# main.net
KiCad netlist of a schematic drawn in Altium Designer
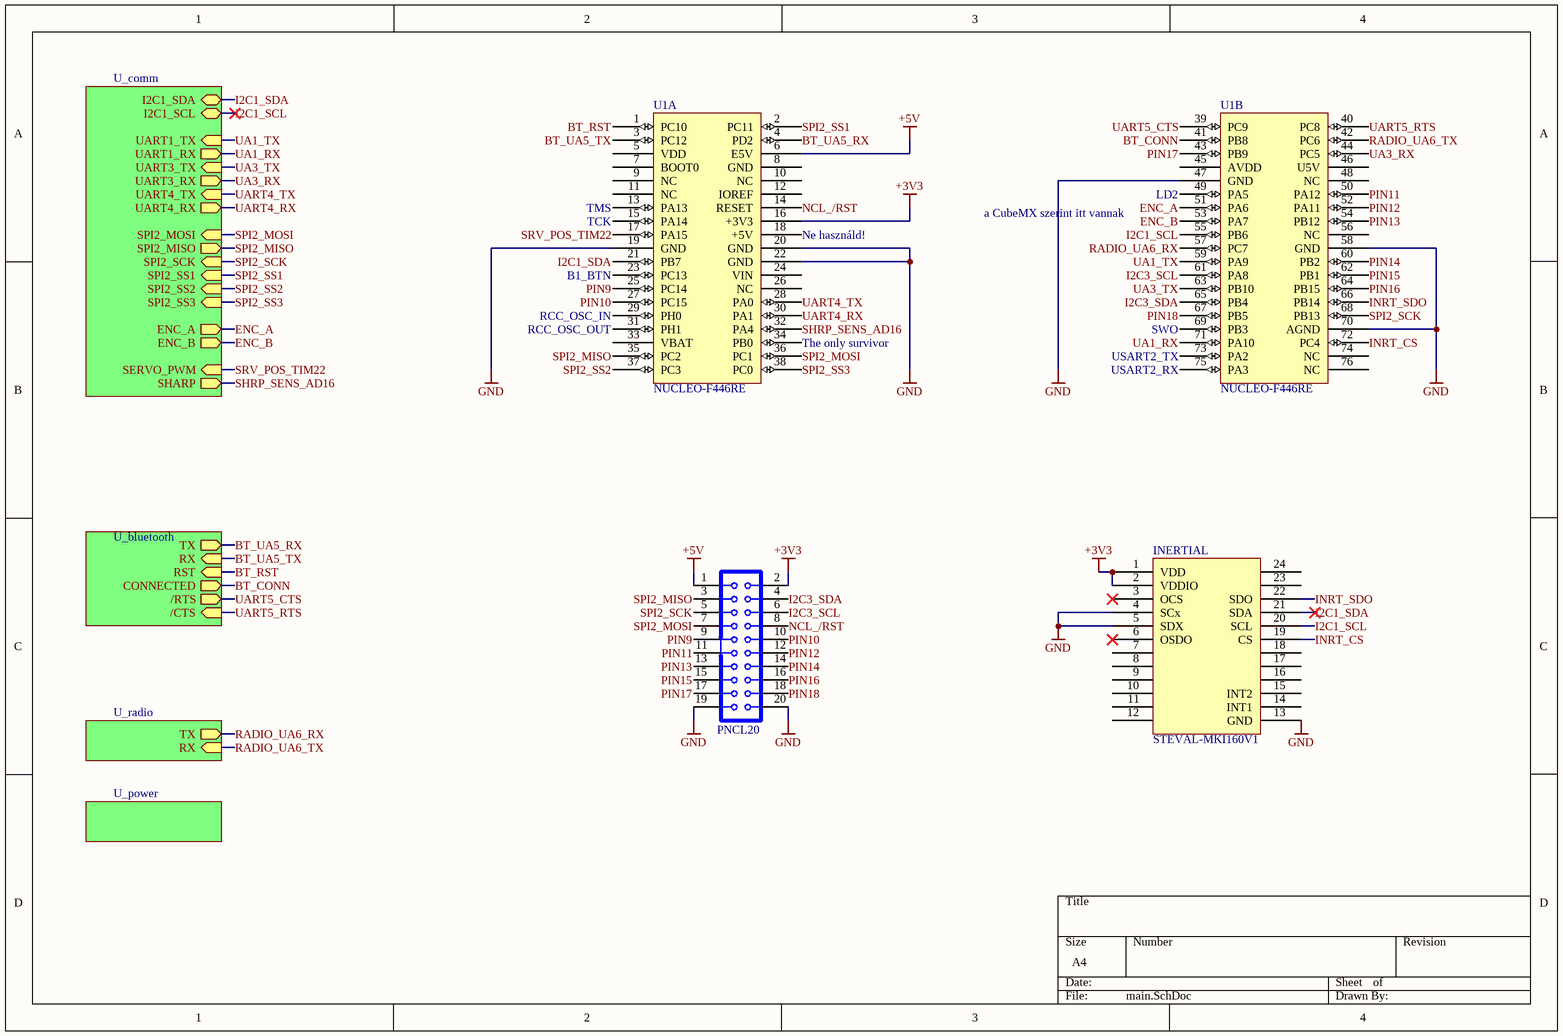
[diagram p0: main.SchDoc]

(export (version "E")
  (design (tool "Eeschema 10.0.6"))
  (components
    (comp (ref "INERTIAL")
      (value "STEVAL-MKI160V1")
      (footprint "STEVAL-MKI160V1")
      (libsource (lib "mb") (part "STEVAL-MKI160V1"))
    )
    (comp (ref "PNCL20")
      (value "Ribbon cable 20")
      (footprint "HDR2X10")
      (libsource (lib "PJ_POWER") (part "Ribbon cable 20"))
    )
    (comp (ref "U1")
      (value "NUCLEO-F446RE")
      (footprint "FP_NUCLEO-64")
      (libsource (lib "hallglib") (part "NUCLEO-F446RE"))
    )
  )
  (nets
    (net (code "1") (name "+3V3") (class "Default")
      (node (ref "INERTIAL") (pin "1") (pinfunction "VDD_1") (pintype "power_in"))
      (node (ref "INERTIAL") (pin "2") (pinfunction "VDDIO_2") (pintype "power_in"))
      (node (ref "PNCL20") (pin "2") (pinfunction "2_2") (pintype "passive"))
      (node (ref "U1") (pin "16") (pinfunction "+3V3_16") (pintype "power_in"))
    )
    (net (code "2") (name "+5V") (class "Default")
      (node (ref "PNCL20") (pin "1") (pinfunction "1_1") (pintype "passive"))
      (node (ref "U1") (pin "6") (pinfunction "E5V_6") (pintype "power_in"))
    )
    (net (code "3") (name "/BT_CONN") (class "Default")
      (node (ref "U1") (pin "41") (pinfunction "PB8_41") (pintype "bidirectional"))
    )
    (net (code "4") (name "/BT_RST") (class "Default")
      (node (ref "U1") (pin "1") (pinfunction "PC10_1") (pintype "bidirectional"))
    )
    (net (code "5") (name "/BT_UA5_RX") (class "Default")
      (node (ref "U1") (pin "4") (pinfunction "PD2_4") (pintype "bidirectional"))
    )
    (net (code "6") (name "/BT_UA5_TX") (class "Default")
      (node (ref "U1") (pin "3") (pinfunction "PC12_3") (pintype "bidirectional"))
    )
    (net (code "7") (name "/ENC_A") (class "Default")
      (node (ref "U1") (pin "51") (pinfunction "PA6_51") (pintype "bidirectional"))
    )
    (net (code "8") (name "/ENC_B") (class "Default")
      (node (ref "U1") (pin "53") (pinfunction "PA7_53") (pintype "bidirectional"))
    )
    (net (code "9") (name "/I2C1_SCL") (class "Default")
      (node (ref "INERTIAL") (pin "20") (pinfunction "SCL_20") (pintype "power_in"))
      (node (ref "U1") (pin "55") (pinfunction "PB6_55") (pintype "bidirectional"))
    )
    (net (code "10") (name "/I2C1_SDA") (class "Default")
      (node (ref "INERTIAL") (pin "21") (pinfunction "SDA_21") (pintype "power_in"))
      (node (ref "U1") (pin "21") (pinfunction "PB7_21") (pintype "bidirectional"))
    )
    (net (code "11") (name "/I2C3_SCL") (class "Default")
      (node (ref "PNCL20") (pin "6") (pinfunction "6_6") (pintype "passive"))
      (node (ref "U1") (pin "61") (pinfunction "PA8_61") (pintype "bidirectional"))
    )
    (net (code "12") (name "/I2C3_SDA") (class "Default")
      (node (ref "PNCL20") (pin "4") (pinfunction "4_4") (pintype "passive"))
      (node (ref "U1") (pin "65") (pinfunction "PB4_65") (pintype "bidirectional"))
    )
    (net (code "13") (name "/INRT_CS") (class "Default")
      (node (ref "INERTIAL") (pin "19") (pinfunction "CS_19") (pintype "power_in"))
      (node (ref "U1") (pin "72") (pinfunction "PC4_72") (pintype "bidirectional"))
    )
    (net (code "14") (name "/INRT_SDO") (class "Default")
      (node (ref "INERTIAL") (pin "22") (pinfunction "SDO_22") (pintype "power_in"))
      (node (ref "U1") (pin "66") (pinfunction "PB14_66") (pintype "bidirectional"))
    )
    (net (code "15") (name "/NCL_{slash}RST") (class "Default")
      (node (ref "PNCL20") (pin "8") (pinfunction "8_8") (pintype "passive"))
      (node (ref "U1") (pin "14") (pinfunction "RESET_14") (pintype "passive"))
    )
    (net (code "16") (name "/PIN9") (class "Default")
      (node (ref "PNCL20") (pin "9") (pinfunction "9_9") (pintype "passive"))
      (node (ref "U1") (pin "25") (pinfunction "PC14_25") (pintype "bidirectional"))
    )
    (net (code "17") (name "/PIN10") (class "Default")
      (node (ref "PNCL20") (pin "10") (pinfunction "10_10") (pintype "passive"))
      (node (ref "U1") (pin "27") (pinfunction "PC15_27") (pintype "bidirectional"))
    )
    (net (code "18") (name "/PIN11") (class "Default")
      (node (ref "PNCL20") (pin "11") (pinfunction "11_11") (pintype "passive"))
      (node (ref "U1") (pin "50") (pinfunction "PA12_50") (pintype "bidirectional"))
    )
    (net (code "19") (name "/PIN12") (class "Default")
      (node (ref "PNCL20") (pin "12") (pinfunction "12_12") (pintype "passive"))
      (node (ref "U1") (pin "52") (pinfunction "PA11_52") (pintype "bidirectional"))
    )
    (net (code "20") (name "/PIN13") (class "Default")
      (node (ref "PNCL20") (pin "13") (pinfunction "13_13") (pintype "passive"))
      (node (ref "U1") (pin "54") (pinfunction "PB12_54") (pintype "bidirectional"))
    )
    (net (code "21") (name "/PIN14") (class "Default")
      (node (ref "PNCL20") (pin "14") (pinfunction "14_14") (pintype "passive"))
      (node (ref "U1") (pin "60") (pinfunction "PB2_60") (pintype "bidirectional"))
    )
    (net (code "22") (name "/PIN15") (class "Default")
      (node (ref "PNCL20") (pin "15") (pinfunction "15_15") (pintype "passive"))
      (node (ref "U1") (pin "62") (pinfunction "PB1_62") (pintype "bidirectional"))
    )
    (net (code "23") (name "/PIN16") (class "Default")
      (node (ref "PNCL20") (pin "16") (pinfunction "16_16") (pintype "passive"))
      (node (ref "U1") (pin "64") (pinfunction "PB15_64") (pintype "bidirectional"))
    )
    (net (code "24") (name "/PIN17") (class "Default")
      (node (ref "PNCL20") (pin "17") (pinfunction "17_17") (pintype "passive"))
      (node (ref "U1") (pin "43") (pinfunction "PB9_43") (pintype "bidirectional"))
    )
    (net (code "25") (name "/PIN18") (class "Default")
      (node (ref "PNCL20") (pin "18") (pinfunction "18_18") (pintype "passive"))
      (node (ref "U1") (pin "67") (pinfunction "PB5_67") (pintype "bidirectional"))
    )
    (net (code "26") (name "/RADIO_UA6_RX") (class "Default")
      (node (ref "U1") (pin "57") (pinfunction "PC7_57") (pintype "bidirectional"))
    )
    (net (code "27") (name "/RADIO_UA6_TX") (class "Default")
      (node (ref "U1") (pin "42") (pinfunction "PC6_42") (pintype "bidirectional"))
    )
    (net (code "28") (name "/SHRP_SENS_AD16") (class "Default")
      (node (ref "U1") (pin "32") (pinfunction "PA4_32") (pintype "bidirectional"))
    )
    (net (code "29") (name "/SPI2_MISO") (class "Default")
      (node (ref "PNCL20") (pin "3") (pinfunction "3_3") (pintype "passive"))
      (node (ref "U1") (pin "35") (pinfunction "PC2_35") (pintype "bidirectional"))
    )
    (net (code "30") (name "/SPI2_MOSI") (class "Default")
      (node (ref "PNCL20") (pin "7") (pinfunction "7_7") (pintype "passive"))
      (node (ref "U1") (pin "36") (pinfunction "PC1_36") (pintype "bidirectional"))
    )
    (net (code "31") (name "/SPI2_SCK") (class "Default")
      (node (ref "PNCL20") (pin "5") (pinfunction "5_5") (pintype "passive"))
      (node (ref "U1") (pin "68") (pinfunction "PB13_68") (pintype "bidirectional"))
    )
    (net (code "32") (name "/SPI2_SS1") (class "Default")
      (node (ref "U1") (pin "2") (pinfunction "PC11_2") (pintype "bidirectional"))
    )
    (net (code "33") (name "/SPI2_SS2") (class "Default")
      (node (ref "U1") (pin "37") (pinfunction "PC3_37") (pintype "bidirectional"))
    )
    (net (code "34") (name "/SPI2_SS3") (class "Default")
      (node (ref "U1") (pin "38") (pinfunction "PC0_38") (pintype "bidirectional"))
    )
    (net (code "35") (name "/SRV_POS_TIM22") (class "Default")
      (node (ref "U1") (pin "17") (pinfunction "PA15_17") (pintype "bidirectional"))
    )
    (net (code "36") (name "/UA1_RX") (class "Default")
      (node (ref "U1") (pin "71") (pinfunction "PA10_71") (pintype "bidirectional"))
    )
    (net (code "37") (name "/UA1_TX") (class "Default")
      (node (ref "U1") (pin "59") (pinfunction "PA9_59") (pintype "bidirectional"))
    )
    (net (code "38") (name "/UA3_RX") (class "Default")
      (node (ref "U1") (pin "44") (pinfunction "PC5_44") (pintype "bidirectional"))
    )
    (net (code "39") (name "/UA3_TX") (class "Default")
      (node (ref "U1") (pin "63") (pinfunction "PB10_63") (pintype "bidirectional"))
    )
    (net (code "40") (name "/UART4_RX") (class "Default")
      (node (ref "U1") (pin "30") (pinfunction "PA1_30") (pintype "bidirectional"))
    )
    (net (code "41") (name "/UART4_TX") (class "Default")
      (node (ref "U1") (pin "28") (pinfunction "PA0_28") (pintype "bidirectional"))
    )
    (net (code "42") (name "/UART5_CTS") (class "Default")
      (node (ref "U1") (pin "39") (pinfunction "PC9_39") (pintype "bidirectional"))
    )
    (net (code "43") (name "/UART5_RTS") (class "Default")
      (node (ref "U1") (pin "40") (pinfunction "PC8_40") (pintype "bidirectional"))
    )
    (net (code "44") (name "GND") (class "Default")
      (node (ref "INERTIAL") (pin "13") (pinfunction "GND_13") (pintype "power_in"))
      (node (ref "INERTIAL") (pin "4") (pinfunction "SCx_4") (pintype "power_in"))
      (node (ref "INERTIAL") (pin "5") (pinfunction "SDX_5") (pintype "power_in"))
      (node (ref "PNCL20") (pin "19") (pinfunction "19_19") (pintype "passive"))
      (node (ref "PNCL20") (pin "20") (pinfunction "20_20") (pintype "passive"))
      (node (ref "U1") (pin "19") (pinfunction "GND_19") (pintype "passive"))
      (node (ref "U1") (pin "20") (pinfunction "GND_20") (pintype "passive"))
      (node (ref "U1") (pin "22") (pinfunction "GND_22") (pintype "passive"))
      (node (ref "U1") (pin "47") (pinfunction "GND_47") (pintype "passive"))
      (node (ref "U1") (pin "58") (pinfunction "GND_58") (pintype "passive"))
      (node (ref "U1") (pin "70") (pinfunction "AGND_70") (pintype "passive"))
    )
    (net (code "45") (name "unconnected-(INERTIAL-INT1-Pad14)") (class "Default")
      (node (ref "INERTIAL") (pin "14") (pinfunction "INT1_14") (pintype "power_in"))
    )
    (net (code "46") (name "unconnected-(INERTIAL-INT2-Pad15)") (class "Default")
      (node (ref "INERTIAL") (pin "15") (pinfunction "INT2_15") (pintype "power_in"))
    )
    (net (code "47") (name "unconnected-(INERTIAL-OCS-Pad3)") (class "Default")
      (node (ref "INERTIAL") (pin "3") (pinfunction "OCS_3") (pintype "power_in+no_connect"))
    )
    (net (code "48") (name "unconnected-(INERTIAL-OSDO-Pad6)") (class "Default")
      (node (ref "INERTIAL") (pin "6") (pinfunction "OSDO_6") (pintype "power_in+no_connect"))
    )
    (net (code "49") (name "unconnected-(INERTIAL-Pad7)") (class "Default")
      (node (ref "INERTIAL") (pin "7") (pintype "power_in"))
    )
    (net (code "50") (name "unconnected-(INERTIAL-Pad8)") (class "Default")
      (node (ref "INERTIAL") (pin "8") (pintype "power_in"))
    )
    (net (code "51") (name "unconnected-(INERTIAL-Pad9)") (class "Default")
      (node (ref "INERTIAL") (pin "9") (pintype "power_in"))
    )
    (net (code "52") (name "unconnected-(INERTIAL-Pad10)") (class "Default")
      (node (ref "INERTIAL") (pin "10") (pintype "power_in"))
    )
    (net (code "53") (name "unconnected-(INERTIAL-Pad11)") (class "Default")
      (node (ref "INERTIAL") (pin "11") (pintype "power_in"))
    )
    (net (code "54") (name "unconnected-(INERTIAL-Pad12)") (class "Default")
      (node (ref "INERTIAL") (pin "12") (pintype "power_in"))
    )
    (net (code "55") (name "unconnected-(INERTIAL-Pad16)") (class "Default")
      (node (ref "INERTIAL") (pin "16") (pintype "power_in"))
    )
    (net (code "56") (name "unconnected-(INERTIAL-Pad17)") (class "Default")
      (node (ref "INERTIAL") (pin "17") (pintype "power_in"))
    )
    (net (code "57") (name "unconnected-(INERTIAL-Pad18)") (class "Default")
      (node (ref "INERTIAL") (pin "18") (pintype "power_in"))
    )
    (net (code "58") (name "unconnected-(INERTIAL-Pad23)") (class "Default")
      (node (ref "INERTIAL") (pin "23") (pintype "power_in"))
    )
    (net (code "59") (name "unconnected-(INERTIAL-Pad24)") (class "Default")
      (node (ref "INERTIAL") (pin "24") (pintype "power_in"))
    )
    (net (code "60") (name "unconnected-(U1A-+5V-Pad18)") (class "Default")
      (node (ref "U1") (pin "18") (pinfunction "+5V_18") (pintype "power_in"))
    )
    (net (code "61") (name "unconnected-(U1A-BOOT0-Pad7)") (class "Default")
      (node (ref "U1") (pin "7") (pinfunction "BOOT0_7") (pintype "passive"))
    )
    (net (code "62") (name "unconnected-(U1A-GND-Pad8)") (class "Default")
      (node (ref "U1") (pin "8") (pinfunction "GND_8") (pintype "passive"))
    )
    (net (code "63") (name "unconnected-(U1A-IOREF-Pad12)") (class "Default")
      (node (ref "U1") (pin "12") (pinfunction "IOREF_12") (pintype "passive"))
    )
    (net (code "64") (name "unconnected-(U1A-NC-Pad9)") (class "Default")
      (node (ref "U1") (pin "9") (pinfunction "NC_9") (pintype "passive"))
    )
    (net (code "65") (name "unconnected-(U1A-NC-Pad10)") (class "Default")
      (node (ref "U1") (pin "10") (pinfunction "NC_10") (pintype "passive"))
    )
    (net (code "66") (name "unconnected-(U1A-NC-Pad11)") (class "Default")
      (node (ref "U1") (pin "11") (pinfunction "NC_11") (pintype "passive"))
    )
    (net (code "67") (name "unconnected-(U1A-NC-Pad26)") (class "Default")
      (node (ref "U1") (pin "26") (pinfunction "NC_26") (pintype "passive"))
    )
    (net (code "68") (name "unconnected-(U1A-PA13-Pad13)") (class "Default")
      (node (ref "U1") (pin "13") (pinfunction "PA13_13") (pintype "bidirectional"))
    )
    (net (code "69") (name "unconnected-(U1A-PA14-Pad15)") (class "Default")
      (node (ref "U1") (pin "15") (pinfunction "PA14_15") (pintype "bidirectional"))
    )
    (net (code "70") (name "unconnected-(U1A-PB0-Pad34)") (class "Default")
      (node (ref "U1") (pin "34") (pinfunction "PB0_34") (pintype "bidirectional"))
    )
    (net (code "71") (name "unconnected-(U1A-PC13-Pad23)") (class "Default")
      (node (ref "U1") (pin "23") (pinfunction "PC13_23") (pintype "bidirectional"))
    )
    (net (code "72") (name "unconnected-(U1A-PH0-Pad29)") (class "Default")
      (node (ref "U1") (pin "29") (pinfunction "PH0_29") (pintype "bidirectional"))
    )
    (net (code "73") (name "unconnected-(U1A-PH1-Pad31)") (class "Default")
      (node (ref "U1") (pin "31") (pinfunction "PH1_31") (pintype "bidirectional"))
    )
    (net (code "74") (name "unconnected-(U1A-VBAT-Pad33)") (class "Default")
      (node (ref "U1") (pin "33") (pinfunction "VBAT_33") (pintype "power_in"))
    )
    (net (code "75") (name "unconnected-(U1A-VDD-Pad5)") (class "Default")
      (node (ref "U1") (pin "5") (pinfunction "VDD_5") (pintype "power_in"))
    )
    (net (code "76") (name "unconnected-(U1A-VIN-Pad24)") (class "Default")
      (node (ref "U1") (pin "24") (pinfunction "VIN_24") (pintype "power_in"))
    )
    (net (code "77") (name "unconnected-(U1B-AVDD-Pad45)") (class "Default")
      (node (ref "U1") (pin "45") (pinfunction "AVDD_45") (pintype "power_in"))
    )
    (net (code "78") (name "unconnected-(U1B-NC-Pad48)") (class "Default")
      (node (ref "U1") (pin "48") (pinfunction "NC_48") (pintype "passive"))
    )
    (net (code "79") (name "unconnected-(U1B-NC-Pad56)") (class "Default")
      (node (ref "U1") (pin "56") (pinfunction "NC_56") (pintype "passive"))
    )
    (net (code "80") (name "unconnected-(U1B-NC-Pad74)") (class "Default")
      (node (ref "U1") (pin "74") (pinfunction "NC_74") (pintype "passive"))
    )
    (net (code "81") (name "unconnected-(U1B-NC-Pad76)") (class "Default")
      (node (ref "U1") (pin "76") (pinfunction "NC_76") (pintype "passive"))
    )
    (net (code "82") (name "unconnected-(U1B-PA2-Pad73)") (class "Default")
      (node (ref "U1") (pin "73") (pinfunction "PA2_73") (pintype "bidirectional"))
    )
    (net (code "83") (name "unconnected-(U1B-PA3-Pad75)") (class "Default")
      (node (ref "U1") (pin "75") (pinfunction "PA3_75") (pintype "bidirectional"))
    )
    (net (code "84") (name "unconnected-(U1B-PA5-Pad49)") (class "Default")
      (node (ref "U1") (pin "49") (pinfunction "PA5_49") (pintype "bidirectional"))
    )
    (net (code "85") (name "unconnected-(U1B-PB3-Pad69)") (class "Default")
      (node (ref "U1") (pin "69") (pinfunction "PB3_69") (pintype "bidirectional"))
    )
    (net (code "86") (name "unconnected-(U1B-U5V-Pad46)") (class "Default")
      (node (ref "U1") (pin "46") (pinfunction "U5V_46") (pintype "power_in"))
    )
  )
)
